# Sheet3.net
KiCad netlist of a schematic drawn in Altium Designer
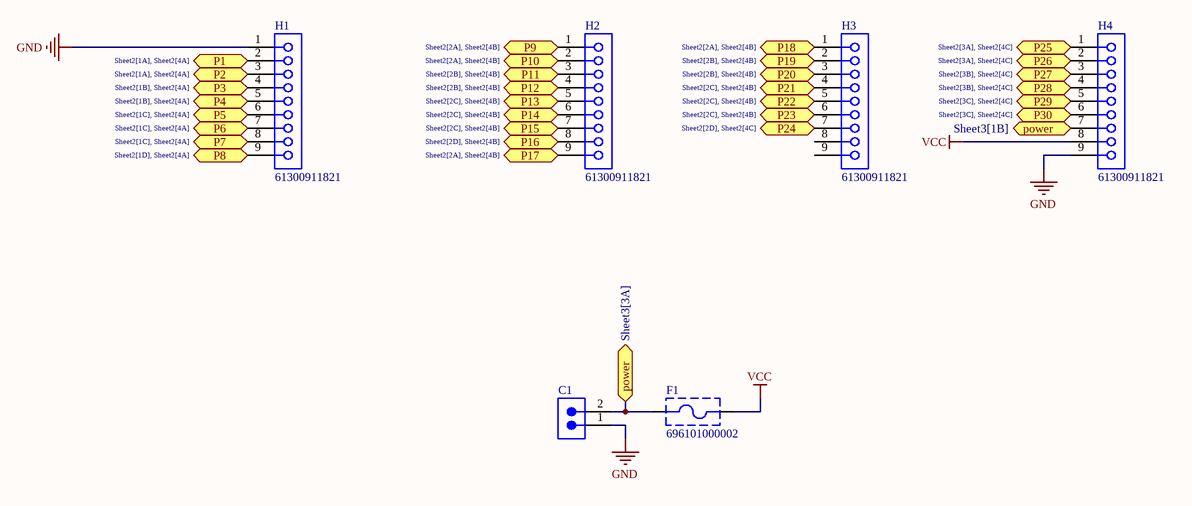
[diagram p0: Sheet3.SchDoc]

(export (version "E")
  (design (tool "Eeschema 10.0.6"))
  (components
    (comp (ref "C1")
      (value "691313510002")
      (footprint "691313510002")
      (description "313; 5.08MM Pitch Straight Pluggable Term Block, Pcb Header, Through Hole, 2 Way")
      (fields (field (name "VOLTAGE") "300V"))
      (libsource (lib "power terminal") (part "CMP-1502-02192-3"))
    )
    (comp (ref "F1")
      (value "696101000002")
      (footprint "696101000002")
      (description "WR-FSH Fuse Holder Blocks Fuse Holder Blocks Clip Cover for PCB")
      (libsource (lib "250v fuse") (part "CMP-1502-00233-4"))
    )
    (comp (ref "H1")
      (value "61300911821")
      (footprint "61300911821")
      (description "THT Vertical Socket Header WR-PHD, Pitch 2.54 mm, Single Row, 9 pins")
      (libsource (lib "9p Female header") (part "CMP-1502-01331-4"))
    )
    (comp (ref "H2")
      (value "61300911821")
      (footprint "61300911821")
      (description "THT Vertical Socket Header WR-PHD, Pitch 2.54 mm, Single Row, 9 pins")
      (libsource (lib "9p Female header") (part "CMP-1502-01331-4"))
    )
    (comp (ref "H3")
      (value "61300911821")
      (footprint "61300911821")
      (description "THT Vertical Socket Header WR-PHD, Pitch 2.54 mm, Single Row, 9 pins")
      (libsource (lib "9p Female header") (part "CMP-1502-01331-4"))
    )
    (comp (ref "H4")
      (value "61300911821")
      (footprint "61300911821")
      (description "THT Vertical Socket Header WR-PHD, Pitch 2.54 mm, Single Row, 9 pins")
      (libsource (lib "9p Female header") (part "CMP-1502-01331-4"))
    )
  )
  (nets
    (net (code "1") (name "/P1") (class "Default")
      (node (ref "H1") (pin "2") (pinfunction "2_2") (pintype "passive"))
    )
    (net (code "2") (name "/P2") (class "Default")
      (node (ref "H1") (pin "3") (pinfunction "3_3") (pintype "passive"))
    )
    (net (code "3") (name "/P3") (class "Default")
      (node (ref "H1") (pin "4") (pinfunction "4_4") (pintype "passive"))
    )
    (net (code "4") (name "/P4") (class "Default")
      (node (ref "H1") (pin "5") (pinfunction "5_5") (pintype "passive"))
    )
    (net (code "5") (name "/P5") (class "Default")
      (node (ref "H1") (pin "6") (pinfunction "6_6") (pintype "passive"))
    )
    (net (code "6") (name "/P6") (class "Default")
      (node (ref "H1") (pin "7") (pinfunction "7_7") (pintype "passive"))
    )
    (net (code "7") (name "/P7") (class "Default")
      (node (ref "H1") (pin "8") (pinfunction "8_8") (pintype "passive"))
    )
    (net (code "8") (name "/P8") (class "Default")
      (node (ref "H1") (pin "9") (pinfunction "9_9") (pintype "passive"))
    )
    (net (code "9") (name "/P9") (class "Default")
      (node (ref "H2") (pin "1") (pinfunction "1_1") (pintype "passive"))
    )
    (net (code "10") (name "/P10") (class "Default")
      (node (ref "H2") (pin "2") (pinfunction "2_2") (pintype "passive"))
    )
    (net (code "11") (name "/P11") (class "Default")
      (node (ref "H2") (pin "3") (pinfunction "3_3") (pintype "passive"))
    )
    (net (code "12") (name "/P12") (class "Default")
      (node (ref "H2") (pin "4") (pinfunction "4_4") (pintype "passive"))
    )
    (net (code "13") (name "/P13") (class "Default")
      (node (ref "H2") (pin "5") (pinfunction "5_5") (pintype "passive"))
    )
    (net (code "14") (name "/P14") (class "Default")
      (node (ref "H2") (pin "6") (pinfunction "6_6") (pintype "passive"))
    )
    (net (code "15") (name "/P15") (class "Default")
      (node (ref "H2") (pin "7") (pinfunction "7_7") (pintype "passive"))
    )
    (net (code "16") (name "/P16") (class "Default")
      (node (ref "H2") (pin "8") (pinfunction "8_8") (pintype "passive"))
    )
    (net (code "17") (name "/P17") (class "Default")
      (node (ref "H2") (pin "9") (pinfunction "9_9") (pintype "passive"))
    )
    (net (code "18") (name "/P18") (class "Default")
      (node (ref "H3") (pin "1") (pinfunction "1_1") (pintype "passive"))
    )
    (net (code "19") (name "/P19") (class "Default")
      (node (ref "H3") (pin "2") (pinfunction "2_2") (pintype "passive"))
    )
    (net (code "20") (name "/P20") (class "Default")
      (node (ref "H3") (pin "3") (pinfunction "3_3") (pintype "passive"))
    )
    (net (code "21") (name "/P21") (class "Default")
      (node (ref "H3") (pin "4") (pinfunction "4_4") (pintype "passive"))
    )
    (net (code "22") (name "/P22") (class "Default")
      (node (ref "H3") (pin "5") (pinfunction "5_5") (pintype "passive"))
    )
    (net (code "23") (name "/P23") (class "Default")
      (node (ref "H3") (pin "6") (pinfunction "6_6") (pintype "passive"))
    )
    (net (code "24") (name "/P24") (class "Default")
      (node (ref "H3") (pin "7") (pinfunction "7_7") (pintype "passive"))
    )
    (net (code "25") (name "/P25") (class "Default")
      (node (ref "H4") (pin "1") (pinfunction "1_1") (pintype "passive"))
    )
    (net (code "26") (name "/P26") (class "Default")
      (node (ref "H4") (pin "2") (pinfunction "2_2") (pintype "passive"))
    )
    (net (code "27") (name "/P27") (class "Default")
      (node (ref "H4") (pin "3") (pinfunction "3_3") (pintype "passive"))
    )
    (net (code "28") (name "/P28") (class "Default")
      (node (ref "H4") (pin "4") (pinfunction "4_4") (pintype "passive"))
    )
    (net (code "29") (name "/P29") (class "Default")
      (node (ref "H4") (pin "5") (pinfunction "5_5") (pintype "passive"))
    )
    (net (code "30") (name "/P30") (class "Default")
      (node (ref "H4") (pin "6") (pinfunction "6_6") (pintype "passive"))
    )
    (net (code "31") (name "/power") (class "Default")
      (node (ref "C1") (pin "2") (pinfunction "2_2") (pintype "passive"))
      (node (ref "F1") (pin "1") (pinfunction "1_1") (pintype "passive"))
      (node (ref "H4") (pin "7") (pinfunction "7_7") (pintype "passive"))
    )
    (net (code "32") (name "GND") (class "Default")
      (node (ref "C1") (pin "1") (pinfunction "1_1") (pintype "passive"))
      (node (ref "H1") (pin "1") (pinfunction "1_1") (pintype "passive"))
      (node (ref "H4") (pin "9") (pinfunction "9_9") (pintype "passive"))
    )
    (net (code "33") (name "VCC") (class "Default")
      (node (ref "F1") (pin "2") (pinfunction "2_2") (pintype "passive"))
      (node (ref "H4") (pin "8") (pinfunction "8_8") (pintype "passive"))
    )
    (net (code "34") (name "unconnected-(H3-Pad8)") (class "Default")
      (node (ref "H3") (pin "8") (pinfunction "8_8") (pintype "passive"))
    )
    (net (code "35") (name "unconnected-(H3-Pad9)") (class "Default")
      (node (ref "H3") (pin "9") (pinfunction "9_9") (pintype "passive"))
    )
  )
)
